# node.net
KiCad netlist of a schematic drawn in EAGLE
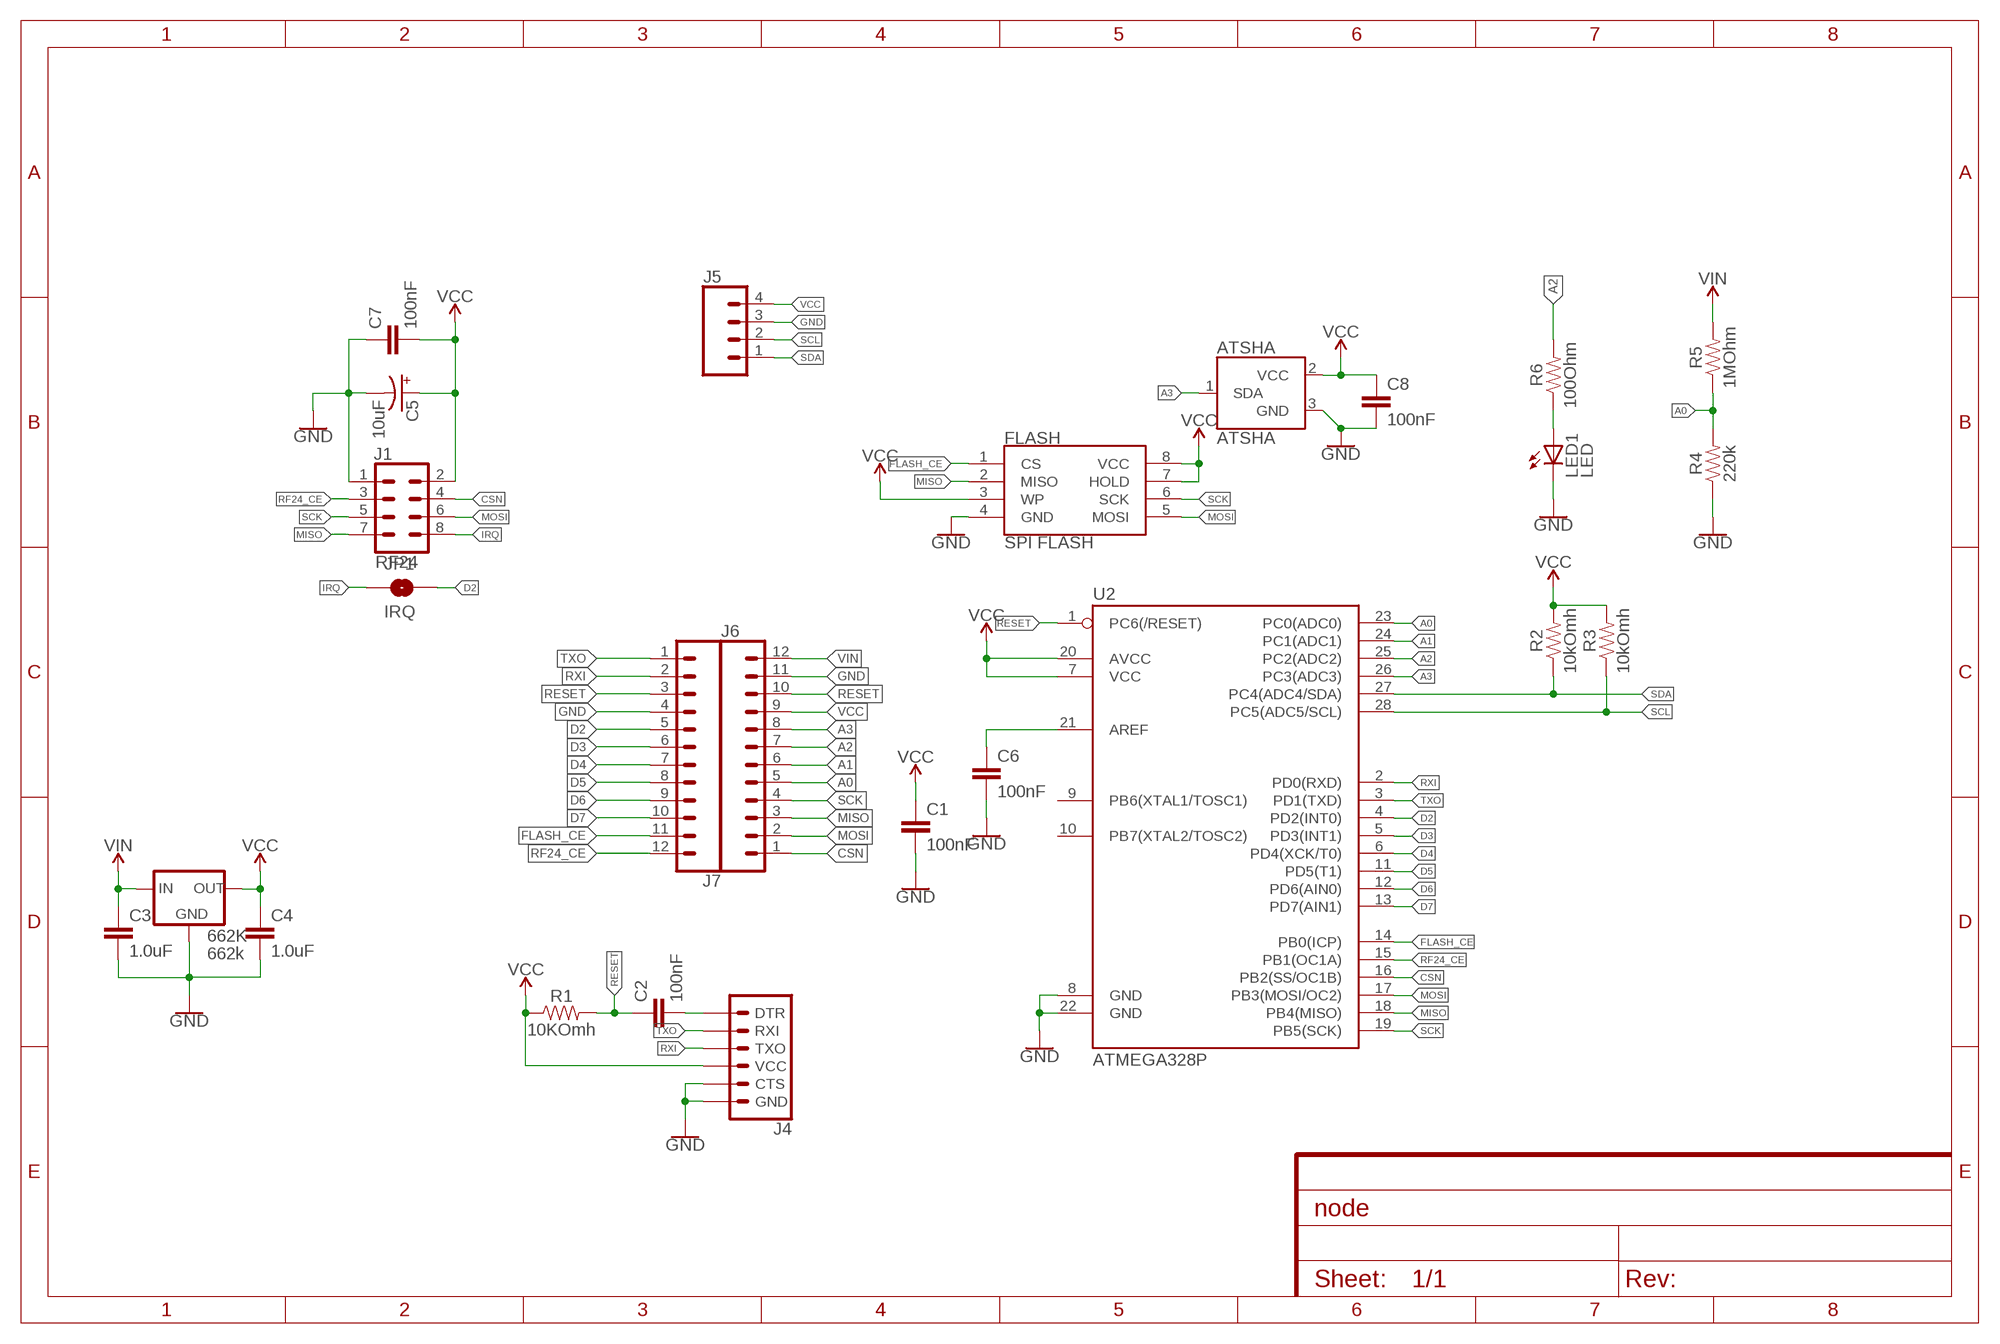
[diagram p0: schematic, sheet 1]

(export (version "E")
  (design (tool "Eeschema 10.0.6"))
  (components
    (comp (ref "662K")
      (value "662k")
      (footprint "eagle-import:SOT23")
      (libsource (lib "eagle-import") (part "XC63FPM"))
    )
    (comp (ref "ATSHA")
      (value "ATSHA")
      (footprint "eagle-import:SOT23-3")
      (libsource (lib "eagle-import") (part "ATSHA204-TSU"))
    )
    (comp (ref "C1")
      (value "100nF")
      (footprint "eagle-import:0805")
      (libsource (lib "eagle-import") (part "10UF-0805-10V-10%"))
    )
    (comp (ref "C2")
      (value "100nF")
      (footprint "eagle-import:0805")
      (libsource (lib "eagle-import") (part "10UF-0805-10V-10%"))
    )
    (comp (ref "C3")
      (value "1.0uF")
      (footprint "eagle-import:0805")
      (libsource (lib "eagle-import") (part "1.0UF-0805-25V-10%"))
    )
    (comp (ref "C4")
      (value "1.0uF")
      (footprint "eagle-import:0805")
      (libsource (lib "eagle-import") (part "1.0UF-0805-25V-10%"))
    )
    (comp (ref "C5")
      (value "10uF")
      (footprint "eagle-import:CPOL-RADIAL-2.5MM-5MM")
      (libsource (lib "eagle-import") (part "10UF-POLAR-RADIAL-2.5MM-25V-20%"))
    )
    (comp (ref "C6")
      (value "100nF")
      (footprint "eagle-import:0805")
      (libsource (lib "eagle-import") (part "10UF-0805-10V-10%"))
    )
    (comp (ref "C7")
      (value "100nF")
      (footprint "eagle-import:0805")
      (libsource (lib "eagle-import") (part "10UF-0805-10V-10%"))
    )
    (comp (ref "C8")
      (value "100nF")
      (footprint "eagle-import:0805")
      (libsource (lib "eagle-import") (part "10UF-0805-10V-10%"))
    )
    (comp (ref "FLASH")
      (value "SPI FLASH")
      (footprint "eagle-import:SO08")
      (libsource (lib "eagle-import") (part "SPI_FLASH-X25XXSMD"))
    )
    (comp (ref "J1")
      (value "RF24")
      (footprint "eagle-import:2X4")
      (libsource (lib "eagle-import") (part "CONN_04X2"))
    )
    (comp (ref "J4")
      (value "6_PIN_SERIAL_TARGET")
      (footprint "eagle-import:1X06")
      (libsource (lib "eagle-import") (part "6_PIN_SERIAL_TARGET"))
    )
    (comp (ref "J5")
      (value "CONN_04")
      (footprint "eagle-import:1X04")
      (libsource (lib "eagle-import") (part "CONN_04"))
    )
    (comp (ref "J6")
      (value "CONN_12")
      (footprint "eagle-import:1X12")
      (libsource (lib "eagle-import") (part "CONN_12"))
    )
    (comp (ref "J7")
      (value "CONN_12")
      (footprint "eagle-import:1X12")
      (libsource (lib "eagle-import") (part "CONN_12"))
    )
    (comp (ref "JP1")
      (value "IRQ")
      (footprint "eagle-import:SMT-JUMPER_2_NO_NO-SILK")
      (libsource (lib "eagle-import") (part "JUMPER-SMT_2_NO_NO-SILK"))
    )
    (comp (ref "LED1")
      (value "LED")
      (footprint "eagle-import:CHIP-LED0805")
      (libsource (lib "eagle-import") (part "LEDCHIP-LED0805"))
    )
    (comp (ref "R1")
      (value "10KOmh")
      (footprint "eagle-import:0805")
      (libsource (lib "eagle-import") (part "RESISTOR0805"))
    )
    (comp (ref "R2")
      (value "10kOmh")
      (footprint "eagle-import:0805")
      (libsource (lib "eagle-import") (part "RESISTOR0805"))
    )
    (comp (ref "R3")
      (value "10kOmh")
      (footprint "eagle-import:0805")
      (libsource (lib "eagle-import") (part "RESISTOR0805"))
    )
    (comp (ref "R4")
      (value "220k")
      (footprint "eagle-import:0805")
      (libsource (lib "eagle-import") (part "RESISTOR0805"))
    )
    (comp (ref "R5")
      (value "1MOhm")
      (footprint "eagle-import:0805")
      (libsource (lib "eagle-import") (part "RESISTOR0805"))
    )
    (comp (ref "R6")
      (value "100Ohm")
      (footprint "eagle-import:0805")
      (libsource (lib "eagle-import") (part "0.22OHM-0805-1/4W-1%"))
    )
    (comp (ref "U2")
      (value "ATMEGA328P")
      (footprint "eagle-import:DIP28")
      (libsource (lib "eagle-import") (part "ATMEGA328P_PDIP"))
    )
  )
  (nets
    (net (code "1") (name "A0") (class "Default")
      (node (ref "J6") (pin "5") (pinfunction "5_5") (pintype "passive"))
      (node (ref "R4") (pin "2") (pinfunction "2_2") (pintype "passive"))
      (node (ref "R5") (pin "1") (pinfunction "1_1") (pintype "passive"))
      (node (ref "U2") (pin "23") (pinfunction "PC0(ADC0)_23") (pintype "bidirectional"))
    )
    (net (code "2") (name "A1") (class "Default")
      (node (ref "J6") (pin "6") (pinfunction "6_6") (pintype "passive"))
      (node (ref "U2") (pin "24") (pinfunction "PC1(ADC1)_24") (pintype "bidirectional"))
    )
    (net (code "3") (name "A2") (class "Default")
      (node (ref "J6") (pin "7") (pinfunction "7_7") (pintype "passive"))
      (node (ref "R6") (pin "2") (pinfunction "2_2") (pintype "passive"))
      (node (ref "U2") (pin "25") (pinfunction "PC2(ADC2)_25") (pintype "bidirectional"))
    )
    (net (code "4") (name "A3") (class "Default")
      (node (ref "ATSHA") (pin "1") (pinfunction "SDA_1") (pintype "bidirectional"))
      (node (ref "J6") (pin "8") (pinfunction "8_8") (pintype "passive"))
      (node (ref "U2") (pin "26") (pinfunction "PC3(ADC3)_26") (pintype "bidirectional"))
    )
    (net (code "5") (name "CSN") (class "Default")
      (node (ref "J1") (pin "4") (pinfunction "4_4") (pintype "passive"))
      (node (ref "J6") (pin "1") (pinfunction "1_1") (pintype "passive"))
      (node (ref "U2") (pin "16") (pinfunction "PB2(SS/OC1B)_16") (pintype "bidirectional"))
    )
    (net (code "6") (name "D2") (class "Default")
      (node (ref "J7") (pin "5") (pinfunction "5_5") (pintype "passive"))
      (node (ref "JP1") (pin "2") (pinfunction "2_2") (pintype "passive"))
      (node (ref "U2") (pin "4") (pinfunction "PD2(INT0)_4") (pintype "bidirectional"))
    )
    (net (code "7") (name "D3") (class "Default")
      (node (ref "J7") (pin "6") (pinfunction "6_6") (pintype "passive"))
      (node (ref "U2") (pin "5") (pinfunction "PD3(INT1)_5") (pintype "bidirectional"))
    )
    (net (code "8") (name "D4") (class "Default")
      (node (ref "J7") (pin "7") (pinfunction "7_7") (pintype "passive"))
      (node (ref "U2") (pin "6") (pinfunction "PD4(XCK/T0)_6") (pintype "bidirectional"))
    )
    (net (code "9") (name "D5") (class "Default")
      (node (ref "J7") (pin "8") (pinfunction "8_8") (pintype "passive"))
      (node (ref "U2") (pin "11") (pinfunction "PD5(T1)_11") (pintype "bidirectional"))
    )
    (net (code "10") (name "D6") (class "Default")
      (node (ref "J7") (pin "9") (pinfunction "9_9") (pintype "passive"))
      (node (ref "U2") (pin "12") (pinfunction "PD6(AIN0)_12") (pintype "bidirectional"))
    )
    (net (code "11") (name "D7") (class "Default")
      (node (ref "J7") (pin "10") (pinfunction "10_10") (pintype "passive"))
      (node (ref "U2") (pin "13") (pinfunction "PD7(AIN1)_13") (pintype "bidirectional"))
    )
    (net (code "12") (name "FLASH_CE") (class "Default")
      (node (ref "FLASH") (pin "1") (pinfunction "CS_1") (pintype "bidirectional"))
      (node (ref "J7") (pin "11") (pinfunction "11_11") (pintype "passive"))
      (node (ref "U2") (pin "14") (pinfunction "PB0(ICP)_14") (pintype "bidirectional"))
    )
    (net (code "13") (name "GND") (class "Default")
      (node (ref "662K") (pin "1") (pinfunction "GND_1") (pintype "input"))
      (node (ref "ATSHA") (pin "3") (pinfunction "GND_3") (pintype "bidirectional"))
      (node (ref "C1") (pin "2") (pinfunction "2_2") (pintype "passive"))
      (node (ref "C3") (pin "2") (pinfunction "2_2") (pintype "passive"))
      (node (ref "C4") (pin "2") (pinfunction "2_2") (pintype "passive"))
      (node (ref "C5") (pin "2") (pinfunction "-_2") (pintype "passive"))
      (node (ref "C6") (pin "2") (pinfunction "2_2") (pintype "passive"))
      (node (ref "C7") (pin "1") (pinfunction "1_1") (pintype "passive"))
      (node (ref "C8") (pin "2") (pinfunction "2_2") (pintype "passive"))
      (node (ref "FLASH") (pin "4") (pinfunction "GND_4") (pintype "power_in"))
      (node (ref "J1") (pin "1") (pinfunction "1_1") (pintype "passive"))
      (node (ref "J4") (pin "5") (pinfunction "CTS_5") (pintype "passive"))
      (node (ref "J4") (pin "6") (pinfunction "GND_6") (pintype "passive"))
      (node (ref "J5") (pin "3") (pinfunction "3_3") (pintype "passive"))
      (node (ref "J6") (pin "11") (pinfunction "11_11") (pintype "passive"))
      (node (ref "J7") (pin "4") (pinfunction "4_4") (pintype "passive"))
      (node (ref "LED1") (pin "C") (pinfunction "C_C") (pintype "passive"))
      (node (ref "R4") (pin "1") (pinfunction "1_1") (pintype "passive"))
      (node (ref "U2") (pin "22") (pinfunction "GND_22") (pintype "bidirectional"))
      (node (ref "U2") (pin "8") (pinfunction "GND_8") (pintype "bidirectional"))
    )
    (net (code "14") (name "IRQ") (class "Default")
      (node (ref "J1") (pin "8") (pinfunction "8_8") (pintype "passive"))
      (node (ref "JP1") (pin "1") (pinfunction "1_1") (pintype "passive"))
    )
    (net (code "15") (name "MISO") (class "Default")
      (node (ref "FLASH") (pin "2") (pinfunction "MISO_2") (pintype "bidirectional"))
      (node (ref "J1") (pin "7") (pinfunction "7_7") (pintype "passive"))
      (node (ref "J6") (pin "3") (pinfunction "3_3") (pintype "passive"))
      (node (ref "U2") (pin "18") (pinfunction "PB4(MISO)_18") (pintype "bidirectional"))
    )
    (net (code "16") (name "MOSI") (class "Default")
      (node (ref "FLASH") (pin "5") (pinfunction "MOSI_5") (pintype "bidirectional"))
      (node (ref "J1") (pin "6") (pinfunction "6_6") (pintype "passive"))
      (node (ref "J6") (pin "2") (pinfunction "2_2") (pintype "passive"))
      (node (ref "U2") (pin "17") (pinfunction "PB3(MOSI/OC2)_17") (pintype "bidirectional"))
    )
    (net (code "17") (name "Net-(J4-DTR)") (class "Default")
      (node (ref "C2") (pin "2") (pinfunction "2_2") (pintype "passive"))
      (node (ref "J4") (pin "1") (pinfunction "DTR_1") (pintype "passive"))
    )
    (net (code "18") (name "Net-(LED1-PadA)") (class "Default")
      (node (ref "LED1") (pin "A") (pinfunction "A_A") (pintype "passive"))
      (node (ref "R6") (pin "1") (pinfunction "1_1") (pintype "passive"))
    )
    (net (code "19") (name "Net-(U2-AREF)") (class "Default")
      (node (ref "C6") (pin "1") (pinfunction "1_1") (pintype "passive"))
      (node (ref "U2") (pin "21") (pinfunction "AREF_21") (pintype "bidirectional"))
    )
    (net (code "20") (name "RESET") (class "Default")
      (node (ref "C2") (pin "1") (pinfunction "1_1") (pintype "passive"))
      (node (ref "J6") (pin "10") (pinfunction "10_10") (pintype "passive"))
      (node (ref "J7") (pin "3") (pinfunction "3_3") (pintype "passive"))
      (node (ref "R1") (pin "2") (pinfunction "2_2") (pintype "passive"))
      (node (ref "U2") (pin "1") (pinfunction "PC6(/RESET)_1") (pintype "bidirectional"))
    )
    (net (code "21") (name "RF24_CE") (class "Default")
      (node (ref "J1") (pin "3") (pinfunction "3_3") (pintype "passive"))
      (node (ref "J7") (pin "12") (pinfunction "12_12") (pintype "passive"))
      (node (ref "U2") (pin "15") (pinfunction "PB1(OC1A)_15") (pintype "bidirectional"))
    )
    (net (code "22") (name "RXI") (class "Default")
      (node (ref "J4") (pin "3") (pinfunction "TXO_3") (pintype "passive"))
      (node (ref "J7") (pin "2") (pinfunction "2_2") (pintype "passive"))
      (node (ref "U2") (pin "2") (pinfunction "PD0(RXD)_2") (pintype "bidirectional"))
    )
    (net (code "23") (name "SCK") (class "Default")
      (node (ref "FLASH") (pin "6") (pinfunction "SCK_6") (pintype "bidirectional"))
      (node (ref "J1") (pin "5") (pinfunction "5_5") (pintype "passive"))
      (node (ref "J6") (pin "4") (pinfunction "4_4") (pintype "passive"))
      (node (ref "U2") (pin "19") (pinfunction "PB5(SCK)_19") (pintype "bidirectional"))
    )
    (net (code "24") (name "SCL") (class "Default")
      (node (ref "J5") (pin "2") (pinfunction "2_2") (pintype "passive"))
      (node (ref "R3") (pin "1") (pinfunction "1_1") (pintype "passive"))
      (node (ref "U2") (pin "28") (pinfunction "PC5(ADC5/SCL)_28") (pintype "bidirectional"))
    )
    (net (code "25") (name "SDA") (class "Default")
      (node (ref "J5") (pin "1") (pinfunction "1_1") (pintype "passive"))
      (node (ref "R2") (pin "1") (pinfunction "1_1") (pintype "passive"))
      (node (ref "U2") (pin "27") (pinfunction "PC4(ADC4/SDA)_27") (pintype "bidirectional"))
    )
    (net (code "26") (name "TXO") (class "Default")
      (node (ref "J4") (pin "2") (pinfunction "RXI_2") (pintype "passive"))
      (node (ref "J7") (pin "1") (pinfunction "1_1") (pintype "passive"))
      (node (ref "U2") (pin "3") (pinfunction "PD1(TXD)_3") (pintype "bidirectional"))
    )
    (net (code "27") (name "VCC") (class "Default")
      (node (ref "662K") (pin "2") (pinfunction "OUT_2") (pintype "passive"))
      (node (ref "ATSHA") (pin "2") (pinfunction "VCC_2") (pintype "bidirectional"))
      (node (ref "C1") (pin "1") (pinfunction "1_1") (pintype "passive"))
      (node (ref "C4") (pin "1") (pinfunction "1_1") (pintype "passive"))
      (node (ref "C5") (pin "1") (pinfunction "+_1") (pintype "passive"))
      (node (ref "C7") (pin "2") (pinfunction "2_2") (pintype "passive"))
      (node (ref "C8") (pin "1") (pinfunction "1_1") (pintype "passive"))
      (node (ref "FLASH") (pin "3") (pinfunction "WP_3") (pintype "bidirectional"))
      (node (ref "FLASH") (pin "7") (pinfunction "HOLD_7") (pintype "bidirectional"))
      (node (ref "FLASH") (pin "8") (pinfunction "VCC_8") (pintype "power_in"))
      (node (ref "J1") (pin "2") (pinfunction "2_2") (pintype "passive"))
      (node (ref "J4") (pin "4") (pinfunction "VCC_4") (pintype "passive"))
      (node (ref "J5") (pin "4") (pinfunction "4_4") (pintype "passive"))
      (node (ref "J6") (pin "9") (pinfunction "9_9") (pintype "passive"))
      (node (ref "R1") (pin "1") (pinfunction "1_1") (pintype "passive"))
      (node (ref "R2") (pin "2") (pinfunction "2_2") (pintype "passive"))
      (node (ref "R3") (pin "2") (pinfunction "2_2") (pintype "passive"))
      (node (ref "U2") (pin "20") (pinfunction "AVCC_20") (pintype "bidirectional"))
      (node (ref "U2") (pin "7") (pinfunction "VCC_7") (pintype "bidirectional"))
    )
    (net (code "28") (name "VIN") (class "Default")
      (node (ref "662K") (pin "3") (pinfunction "IN_3") (pintype "input"))
      (node (ref "C3") (pin "1") (pinfunction "1_1") (pintype "passive"))
      (node (ref "J6") (pin "12") (pinfunction "12_12") (pintype "passive"))
      (node (ref "R5") (pin "2") (pinfunction "2_2") (pintype "passive"))
    )
    (net (code "29") (name "unconnected-(U2-PB6(XTAL1{slash}TOSC1)-Pad9)") (class "Default")
      (node (ref "U2") (pin "9") (pinfunction "PB6(XTAL1/TOSC1)_9") (pintype "bidirectional"))
    )
    (net (code "30") (name "unconnected-(U2-PB7(XTAL2{slash}TOSC2)-Pad10)") (class "Default")
      (node (ref "U2") (pin "10") (pinfunction "PB7(XTAL2/TOSC2)_10") (pintype "bidirectional"))
    )
  )
)
